# lcd.net
KiCad netlist of a schematic drawn in EAGLE
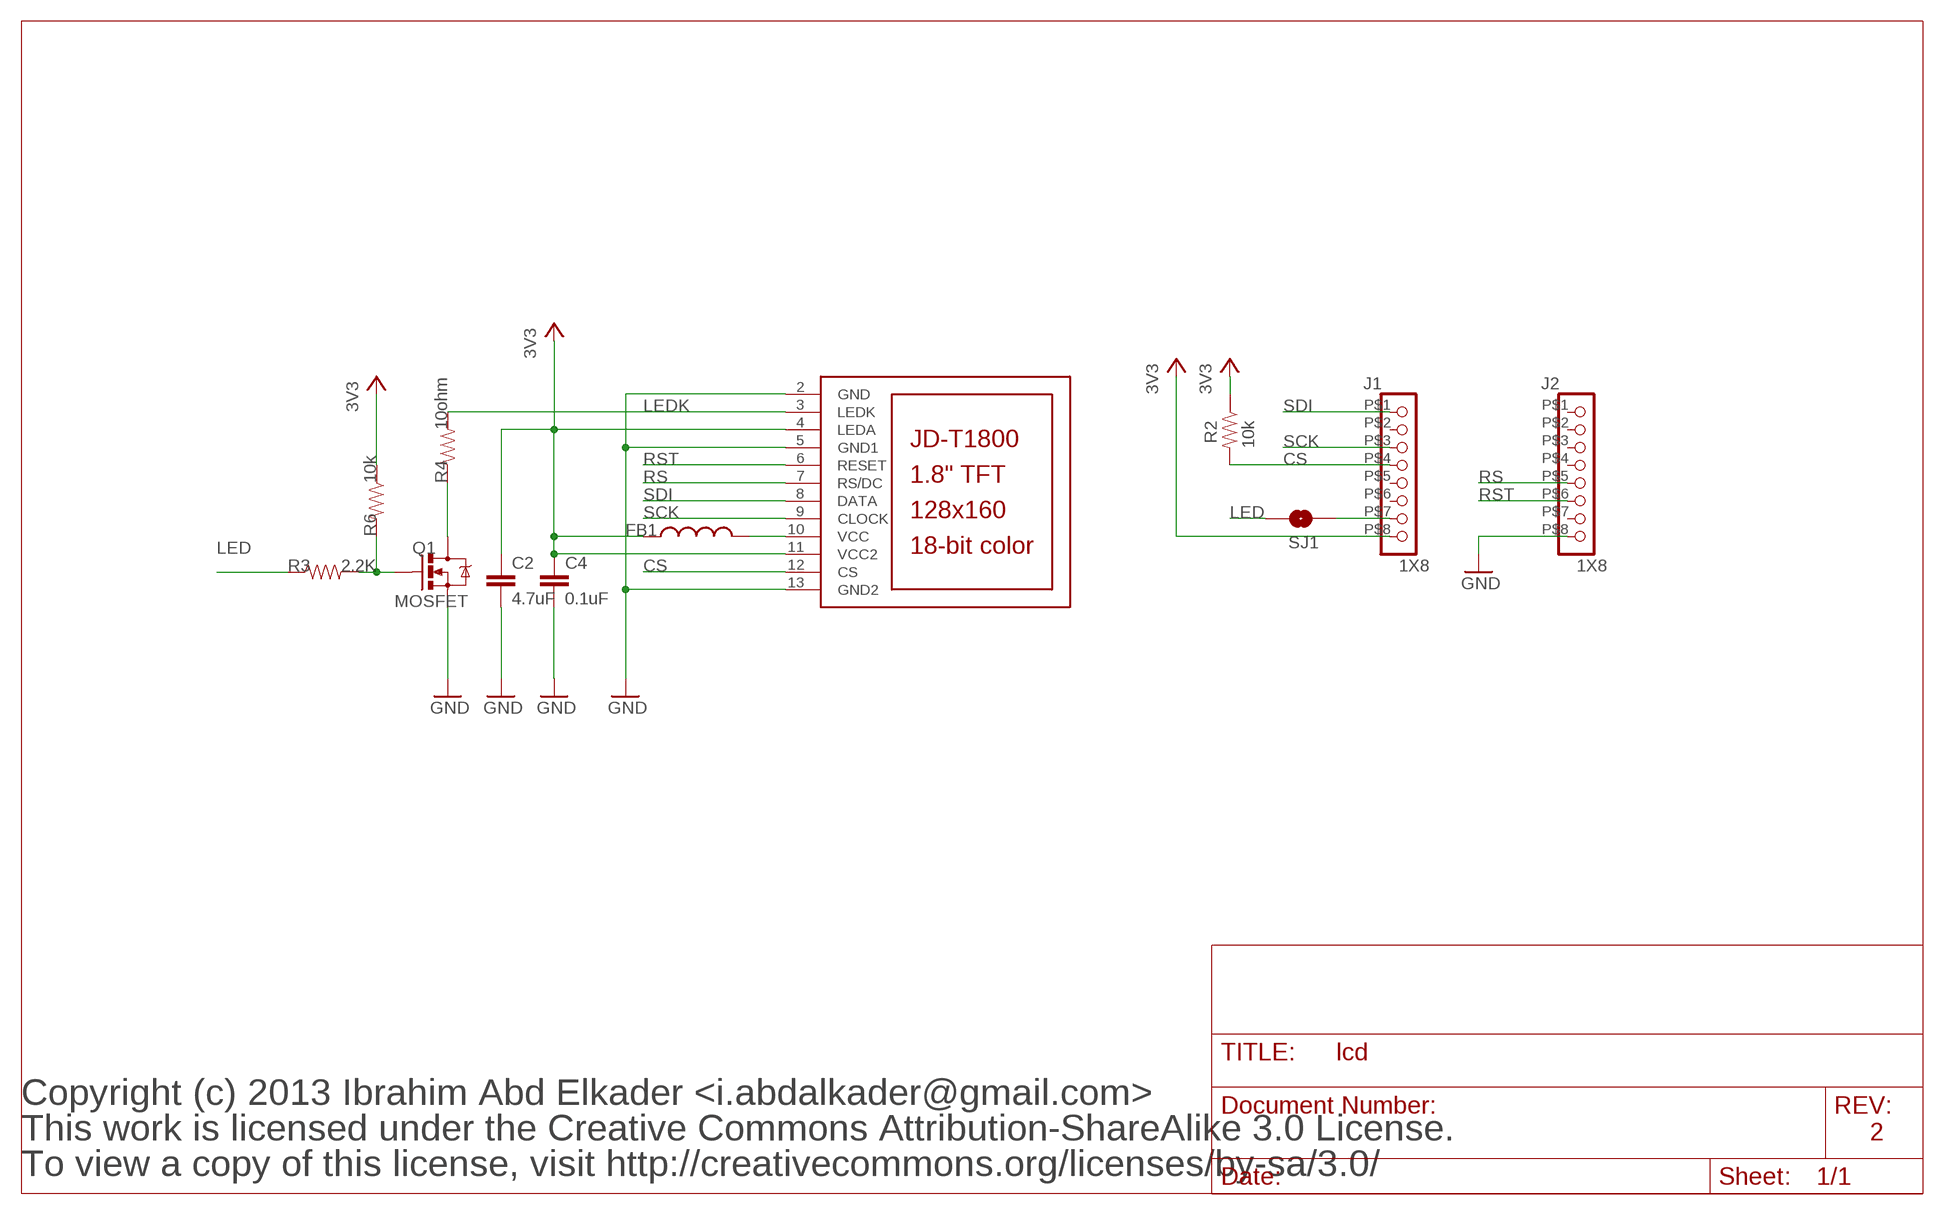
[diagram p0: schematic, sheet 1]

(export (version "E")
  (design (tool "Eeschema 10.0.6"))
  (components
    (comp (ref "C2")
      (value "4.7uF")
      (footprint "eagle-import:0603-CAP")
      (libsource (lib "eagle-import") (part "CAP0603-CAP"))
    )
    (comp (ref "C4")
      (value "0.1uF")
      (footprint "eagle-import:0603-CAP")
      (libsource (lib "eagle-import") (part "CAP0603-CAP"))
    )
    (comp (ref "FB1")
      (value "INDUCTOR0603")
      (footprint "eagle-import:0603")
      (libsource (lib "eagle-import") (part "INDUCTOR0603"))
    )
    (comp (ref "J1")
      (value "1X8")
      (footprint "eagle-import:1X8")
      (libsource (lib "eagle-import") (part "1X8"))
    )
    (comp (ref "J2")
      (value "1X8")
      (footprint "eagle-import:1X8")
      (libsource (lib "eagle-import") (part "1X8"))
    )
    (comp (ref "LCD1")
      (value "JD-T1800")
      (footprint "eagle-import:JD-T1800")
      (libsource (lib "eagle-import") (part "JD-T1800"))
    )
    (comp (ref "Q1")
      (value "MOSFET")
      (footprint "eagle-import:SOT23-3")
      (libsource (lib "eagle-import") (part "MOSFET-NCHANNELSMD"))
    )
    (comp (ref "R2")
      (value "10k")
      (footprint "eagle-import:0603-RES")
      (libsource (lib "eagle-import") (part "RESISTOR0603-RES"))
    )
    (comp (ref "R3")
      (value "2.2K")
      (footprint "eagle-import:0603-RES")
      (libsource (lib "eagle-import") (part "RESISTOR0603-RES"))
    )
    (comp (ref "R4")
      (value "10ohm")
      (footprint "eagle-import:0603-RES")
      (libsource (lib "eagle-import") (part "RESISTOR0603-RES"))
    )
    (comp (ref "R6")
      (value "10k")
      (footprint "eagle-import:0603-RES")
      (libsource (lib "eagle-import") (part "RESISTOR0603-RES"))
    )
    (comp (ref "SJ1")
      (value "SOLDERJUMPERTRACE")
      (footprint "eagle-import:SJ_2S-TRACE")
      (libsource (lib "eagle-import") (part "SOLDERJUMPERTRACE"))
    )
  )
  (nets
    (net (code "1") (name "/CS") (class "Default")
      (node (ref "J1") (pin "P$4") (pinfunction "4_P$4") (pintype "passive"))
      (node (ref "LCD1") (pin "12") (pinfunction "CS_12") (pintype "input"))
      (node (ref "R2") (pin "2") (pinfunction "2_2") (pintype "passive"))
    )
    (net (code "2") (name "/LED") (class "Default")
      (node (ref "R3") (pin "1") (pinfunction "1_1") (pintype "passive"))
      (node (ref "SJ1") (pin "2") (pinfunction "2_2") (pintype "passive"))
    )
    (net (code "3") (name "/LEDK") (class "Default")
      (node (ref "LCD1") (pin "3") (pinfunction "LEDK_3") (pintype "input"))
      (node (ref "R4") (pin "2") (pinfunction "2_2") (pintype "passive"))
    )
    (net (code "4") (name "/RS") (class "Default")
      (node (ref "J2") (pin "P$5") (pinfunction "5_P$5") (pintype "passive"))
      (node (ref "LCD1") (pin "7") (pinfunction "RS/DC_7") (pintype "input"))
    )
    (net (code "5") (name "/RST") (class "Default")
      (node (ref "J2") (pin "P$6") (pinfunction "6_P$6") (pintype "passive"))
      (node (ref "LCD1") (pin "6") (pinfunction "RESET_6") (pintype "input"))
    )
    (net (code "6") (name "/SCK") (class "Default")
      (node (ref "J1") (pin "P$3") (pinfunction "3_P$3") (pintype "passive"))
      (node (ref "LCD1") (pin "9") (pinfunction "CLOCK_9") (pintype "input"))
    )
    (net (code "7") (name "/SDI") (class "Default")
      (node (ref "J1") (pin "P$1") (pinfunction "1_P$1") (pintype "passive"))
      (node (ref "LCD1") (pin "8") (pinfunction "DATA_8") (pintype "bidirectional"))
    )
    (net (code "8") (name "3V3") (class "Default")
      (node (ref "C2") (pin "1") (pinfunction "1_1") (pintype "passive"))
      (node (ref "C4") (pin "1") (pinfunction "1_1") (pintype "passive"))
      (node (ref "FB1") (pin "1") (pinfunction "1_1") (pintype "passive"))
      (node (ref "J1") (pin "P$8") (pinfunction "8_P$8") (pintype "passive"))
      (node (ref "LCD1") (pin "11") (pinfunction "VCC2_11") (pintype "power_in"))
      (node (ref "LCD1") (pin "4") (pinfunction "LEDA_4") (pintype "input"))
      (node (ref "R2") (pin "1") (pinfunction "1_1") (pintype "passive"))
      (node (ref "R6") (pin "1") (pinfunction "1_1") (pintype "passive"))
    )
    (net (code "9") (name "GND") (class "Default")
      (node (ref "C2") (pin "2") (pinfunction "2_2") (pintype "passive"))
      (node (ref "C4") (pin "2") (pinfunction "2_2") (pintype "passive"))
      (node (ref "J2") (pin "P$8") (pinfunction "8_P$8") (pintype "passive"))
      (node (ref "LCD1") (pin "13") (pinfunction "GND2_13") (pintype "power_in"))
      (node (ref "LCD1") (pin "2") (pinfunction "GND_2") (pintype "power_in"))
      (node (ref "LCD1") (pin "5") (pinfunction "GND1_5") (pintype "power_in"))
      (node (ref "Q1") (pin "2") (pinfunction "S_2") (pintype "passive"))
    )
    (net (code "10") (name "Net-(J1-7)") (class "Default")
      (node (ref "J1") (pin "P$7") (pinfunction "7_P$7") (pintype "passive"))
      (node (ref "SJ1") (pin "1") (pinfunction "1_1") (pintype "passive"))
    )
    (net (code "11") (name "Net-(LCD1-VCC)") (class "Default")
      (node (ref "FB1") (pin "2") (pinfunction "2_2") (pintype "passive"))
      (node (ref "LCD1") (pin "10") (pinfunction "VCC_10") (pintype "power_in"))
    )
    (net (code "12") (name "Net-(Q1-D)") (class "Default")
      (node (ref "Q1") (pin "3") (pinfunction "D_3") (pintype "passive"))
      (node (ref "R4") (pin "1") (pinfunction "1_1") (pintype "passive"))
    )
    (net (code "13") (name "Net-(Q1-G)") (class "Default")
      (node (ref "Q1") (pin "1") (pinfunction "G_1") (pintype "passive"))
      (node (ref "R3") (pin "2") (pinfunction "2_2") (pintype "passive"))
      (node (ref "R6") (pin "2") (pinfunction "2_2") (pintype "passive"))
    )
    (net (code "14") (name "unconnected-(J1-2-PadP$2)") (class "Default")
      (node (ref "J1") (pin "P$2") (pinfunction "2_P$2") (pintype "passive"))
    )
    (net (code "15") (name "unconnected-(J1-5-PadP$5)") (class "Default")
      (node (ref "J1") (pin "P$5") (pinfunction "5_P$5") (pintype "passive"))
    )
    (net (code "16") (name "unconnected-(J1-6-PadP$6)") (class "Default")
      (node (ref "J1") (pin "P$6") (pinfunction "6_P$6") (pintype "passive"))
    )
    (net (code "17") (name "unconnected-(J2-1-PadP$1)") (class "Default")
      (node (ref "J2") (pin "P$1") (pinfunction "1_P$1") (pintype "passive"))
    )
    (net (code "18") (name "unconnected-(J2-2-PadP$2)") (class "Default")
      (node (ref "J2") (pin "P$2") (pinfunction "2_P$2") (pintype "passive"))
    )
    (net (code "19") (name "unconnected-(J2-3-PadP$3)") (class "Default")
      (node (ref "J2") (pin "P$3") (pinfunction "3_P$3") (pintype "passive"))
    )
    (net (code "20") (name "unconnected-(J2-4-PadP$4)") (class "Default")
      (node (ref "J2") (pin "P$4") (pinfunction "4_P$4") (pintype "passive"))
    )
    (net (code "21") (name "unconnected-(J2-7-PadP$7)") (class "Default")
      (node (ref "J2") (pin "P$7") (pinfunction "7_P$7") (pintype "passive"))
    )
  )
)
